# one_dollar_boad_beta4.net
KiCad netlist of a schematic drawn in EAGLE
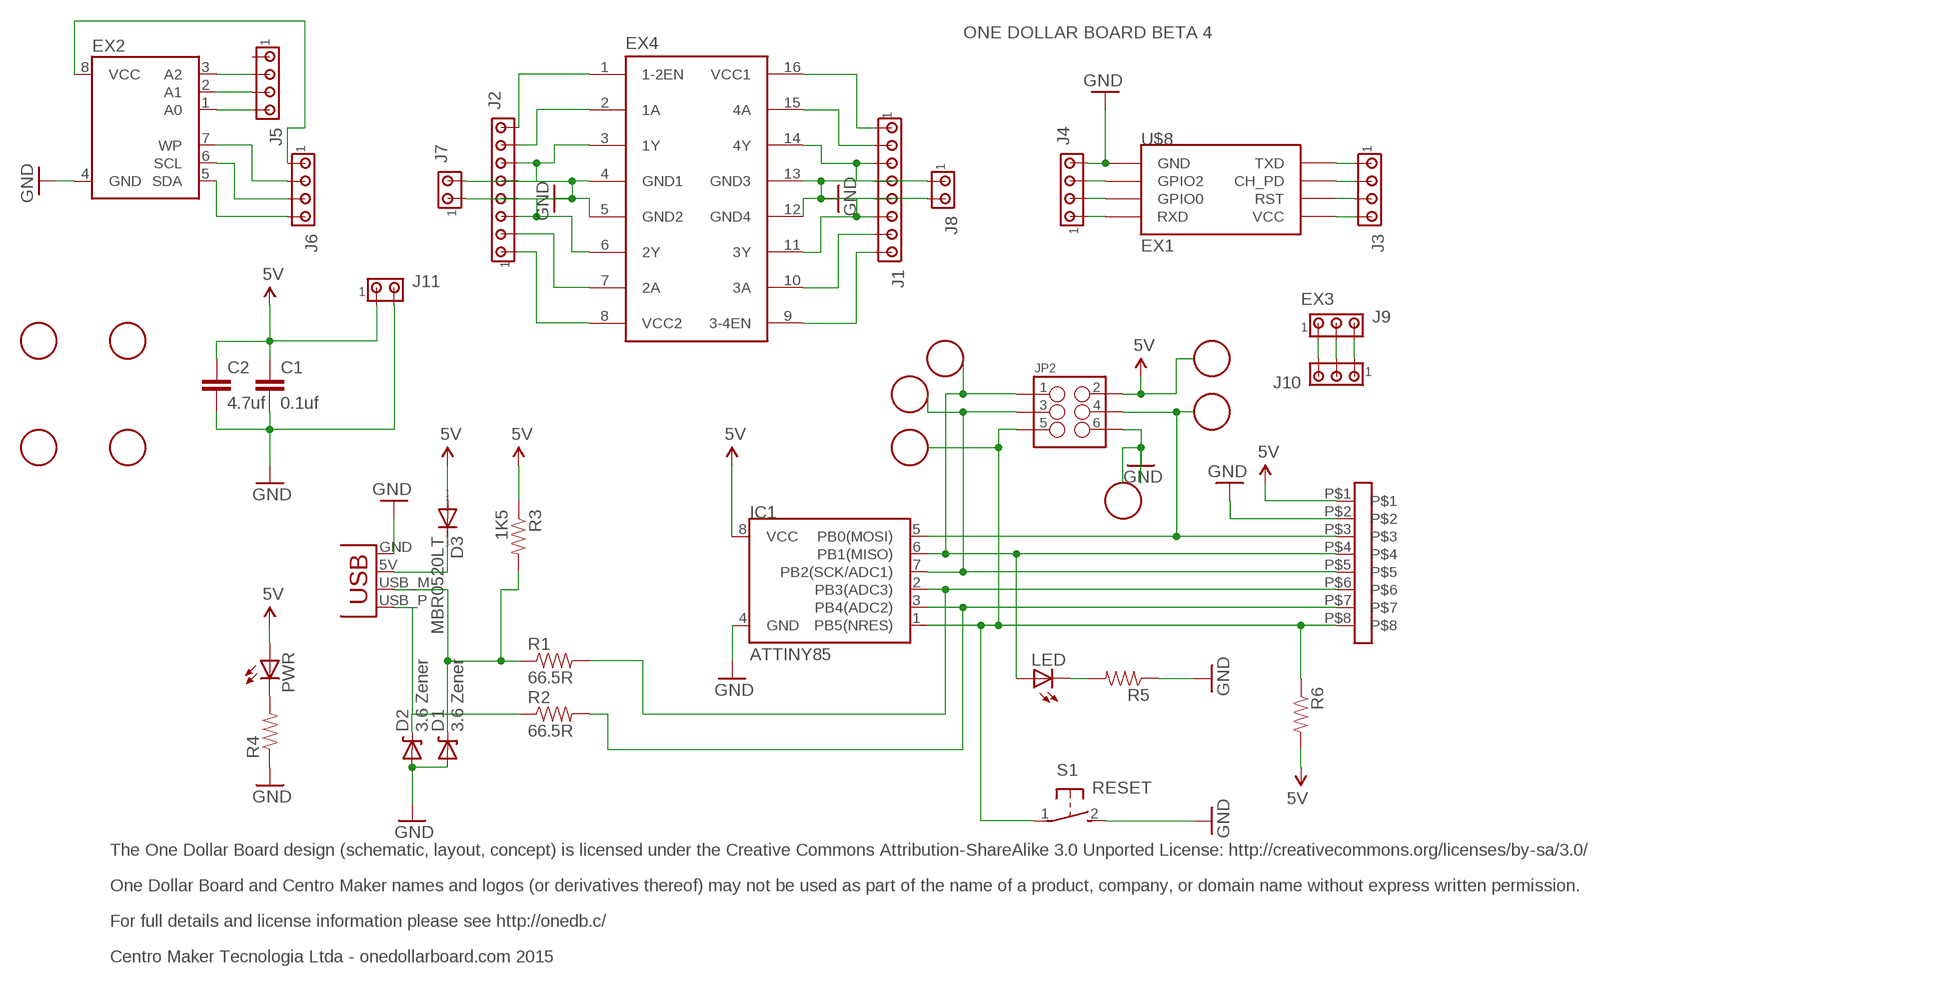
[diagram p0: schematic, sheet 1]

(export (version "E")
  (design (tool "Eeschema 10.0.6"))
  (components
    (comp (ref "C1")
      (value "0.1uf")
      (footprint "eagle-import:0402-CAP")
      (libsource (lib "eagle-import") (part "CAP0402-CAP"))
    )
    (comp (ref "C2")
      (value "4.7uf")
      (footprint "eagle-import:0805")
      (libsource (lib "eagle-import") (part "CAP0805"))
    )
    (comp (ref "CONNECTORBAR1")
      (value ".")
      (footprint "eagle-import:FEMEABARRA01X08")
      (libsource (lib "eagle-import") (part "FAMALEBAR01X08"))
    )
    (comp (ref "D1")
      (value "3.6 Zener")
      (footprint "eagle-import:SOD-323")
      (libsource (lib "eagle-import") (part "DIODE-ZENER-BZT52"))
    )
    (comp (ref "D2")
      (value "3.6 Zener")
      (footprint "eagle-import:SOD-323")
      (libsource (lib "eagle-import") (part "DIODE-ZENER-BZT52"))
    )
    (comp (ref "D3")
      (value "MBR0520LT")
      (footprint "eagle-import:SOD123")
      (libsource (lib "eagle-import") (part "MBR0520LT"))
    )
    (comp (ref "EX2")
      (value "AT24CP")
      (footprint "eagle-import:DIL08")
      (fields (field (name "MPN") "AT24C1024BW-SH-B"))
      (libsource (lib "eagle-import") (part "AT24CP"))
    )
    (comp (ref "EX4")
      (value "L293D")
      (footprint "eagle-import:DIL16")
      (libsource (lib "eagle-import") (part "L293D"))
    )
    (comp (ref "IC1")
      (value "ATTINY85")
      (footprint "eagle-import:SO08-EIAJ")
      (libsource (lib "eagle-import") (part "ATTINY45"))
    )
    (comp (ref "ICSP1")
      (value "ICSP")
      (footprint "eagle-import:ICSP")
      (libsource (lib "eagle-import") (part "ICSP"))
    )
    (comp (ref "ICSP2")
      (value "ICSP")
      (footprint "eagle-import:ICSP")
      (libsource (lib "eagle-import") (part "ICSP"))
    )
    (comp (ref "ICSP3")
      (value "ICSP")
      (footprint "eagle-import:ICSP")
      (libsource (lib "eagle-import") (part "ICSP"))
    )
    (comp (ref "ICSP4")
      (value "ICSP")
      (footprint "eagle-import:ICSP")
      (libsource (lib "eagle-import") (part "ICSP"))
    )
    (comp (ref "ICSP5")
      (value "ICSP")
      (footprint "eagle-import:ICSP")
      (libsource (lib "eagle-import") (part "ICSP"))
    )
    (comp (ref "ICSP6")
      (value "ICSP")
      (footprint "eagle-import:ICSP")
      (libsource (lib "eagle-import") (part "ICSP"))
    )
    (comp (ref "J1")
      (value "MTA08-100")
      (footprint "eagle-import:10X08MTA")
      (libsource (lib "eagle-import") (part "MTA08-100"))
    )
    (comp (ref "J2")
      (value "MTA08-100")
      (footprint "eagle-import:10X08MTA")
      (libsource (lib "eagle-import") (part "MTA08-100"))
    )
    (comp (ref "J3")
      (value "MTA04-100")
      (footprint "eagle-import:10X04MTA")
      (libsource (lib "eagle-import") (part "MTA04-100"))
    )
    (comp (ref "J4")
      (value "MTA04-100")
      (footprint "eagle-import:10X04MTA")
      (libsource (lib "eagle-import") (part "MTA04-100"))
    )
    (comp (ref "J5")
      (value "MTA04-100")
      (footprint "eagle-import:10X04MTA")
      (libsource (lib "eagle-import") (part "MTA04-100"))
    )
    (comp (ref "J6")
      (value "MTA04-100")
      (footprint "eagle-import:10X04MTA")
      (libsource (lib "eagle-import") (part "MTA04-100"))
    )
    (comp (ref "J7")
      (value "MTA02-100")
      (footprint "eagle-import:10X02MTA")
      (libsource (lib "eagle-import") (part "MTA02-100"))
    )
    (comp (ref "J8")
      (value "MTA02-100")
      (footprint "eagle-import:10X02MTA")
      (libsource (lib "eagle-import") (part "MTA02-100"))
    )
    (comp (ref "J9")
      (value "MTA03-100")
      (footprint "eagle-import:10X03MTA")
      (libsource (lib "eagle-import") (part "MTA03-100"))
    )
    (comp (ref "J10")
      (value "MTA03-100")
      (footprint "eagle-import:10X03MTA")
      (libsource (lib "eagle-import") (part "MTA03-100"))
    )
    (comp (ref "J11")
      (value "MTA02-100")
      (footprint "eagle-import:10X02MTA")
      (libsource (lib "eagle-import") (part "MTA02-100"))
    )
    (comp (ref "JP2")
      (value "M03X22X3_SILK_MALE_PTH")
      (footprint "eagle-import:2X3")
      (libsource (lib "eagle-import") (part "M03X22X3_SILK_MALE_PTH"))
    )
    (comp (ref "LED")
      (value "LED0603")
      (footprint "eagle-import:LED-0603")
      (libsource (lib "eagle-import") (part "LED0603"))
    )
    (comp (ref "PWR")
      (value "LED0603")
      (footprint "eagle-import:LED-0603")
      (libsource (lib "eagle-import") (part "LED0603"))
    )
    (comp (ref "R1")
      (value "66.5R")
      (footprint "eagle-import:0402-RES")
      (libsource (lib "eagle-import") (part "RESISTOR0402-RES"))
    )
    (comp (ref "R2")
      (value "66.5R")
      (footprint "eagle-import:0402-RES")
      (libsource (lib "eagle-import") (part "RESISTOR0402-RES"))
    )
    (comp (ref "R3")
      (value "1K5")
      (footprint "eagle-import:0402-RES")
      (libsource (lib "eagle-import") (part "RESISTOR0402-RES"))
    )
    (comp (ref "R4")
      (value "RESISTOR0402-RES")
      (footprint "eagle-import:0402-RES")
      (libsource (lib "eagle-import") (part "RESISTOR0402-RES"))
    )
    (comp (ref "R5")
      (value "RESISTOR0402-RES")
      (footprint "eagle-import:0402-RES")
      (libsource (lib "eagle-import") (part "RESISTOR0402-RES"))
    )
    (comp (ref "R6")
      (value "RESISTOR0402-RES")
      (footprint "eagle-import:0402-RES")
      (libsource (lib "eagle-import") (part "RESISTOR0402-RES"))
    )
    (comp (ref "S1")
      (value "RESET")
      (footprint "eagle-import:DTSM-3")
      (libsource (lib "eagle-import") (part "DTSM-3"))
    )
    (comp (ref "U$8")
      (value "EX1")
      (footprint "eagle-import:ESP01")
      (libsource (lib "eagle-import") (part "ESP01"))
    )
    (comp (ref "U$9")
      (value "ARDUINOPINAGEM")
      (footprint "eagle-import:ARDUINOPINAGEM")
      (libsource (lib "eagle-import") (part "ARDUINOPINAGEM"))
    )
    (comp (ref "X1")
      (value "USBPCB")
      (footprint "eagle-import:USB-A-PCB")
      (libsource (lib "eagle-import") (part "USBPCB"))
    )
  )
  (nets
    (net (code "1") (name "5V") (class "Default")
      (node (ref "C1") (pin "1") (pinfunction "1_1") (pintype "passive"))
      (node (ref "C2") (pin "1") (pinfunction "1_1") (pintype "passive"))
      (node (ref "CONNECTORBAR1") (pin "P$1") (pinfunction "P$1_P$1") (pintype "bidirectional"))
      (node (ref "D3") (pin "A") (pinfunction "A_A") (pintype "passive"))
      (node (ref "IC1") (pin "8") (pinfunction "VCC_8") (pintype "bidirectional"))
      (node (ref "J11") (pin "1") (pinfunction "1_1") (pintype "passive"))
      (node (ref "JP2") (pin "2") (pinfunction "2_2") (pintype "bidirectional"))
      (node (ref "PWR") (pin "A") (pinfunction "A_A") (pintype "passive"))
      (node (ref "R3") (pin "1") (pinfunction "1_1") (pintype "passive"))
      (node (ref "R6") (pin "2") (pinfunction "2_2") (pintype "passive"))
    )
    (net (code "2") (name "GND") (class "Default")
      (node (ref "C1") (pin "2") (pinfunction "2_2") (pintype "passive"))
      (node (ref "C2") (pin "2") (pinfunction "2_2") (pintype "passive"))
      (node (ref "CONNECTORBAR1") (pin "P$2") (pinfunction "P$2_P$2") (pintype "bidirectional"))
      (node (ref "D1") (pin "2") (pinfunction "A_2") (pintype "passive"))
      (node (ref "D2") (pin "2") (pinfunction "A_2") (pintype "passive"))
      (node (ref "EX2") (pin "4") (pinfunction "GND_4") (pintype "power_in"))
      (node (ref "EX4") (pin "12") (pinfunction "GND4_12") (pintype "power_in"))
      (node (ref "EX4") (pin "13") (pinfunction "GND3_13") (pintype "power_in"))
      (node (ref "EX4") (pin "4") (pinfunction "GND1_4") (pintype "power_in"))
      (node (ref "EX4") (pin "5") (pinfunction "GND2_5") (pintype "power_in"))
      (node (ref "IC1") (pin "4") (pinfunction "GND_4") (pintype "bidirectional"))
      (node (ref "J1") (pin "4") (pinfunction "4_4") (pintype "passive"))
      (node (ref "J1") (pin "5") (pinfunction "5_5") (pintype "passive"))
      (node (ref "J11") (pin "2") (pinfunction "2_2") (pintype "passive"))
      (node (ref "J2") (pin "4") (pinfunction "4_4") (pintype "passive"))
      (node (ref "J2") (pin "5") (pinfunction "5_5") (pintype "passive"))
      (node (ref "J4") (pin "4") (pinfunction "4_4") (pintype "passive"))
      (node (ref "JP2") (pin "6") (pinfunction "6_6") (pintype "bidirectional"))
      (node (ref "R4") (pin "1") (pinfunction "1_1") (pintype "passive"))
      (node (ref "R5") (pin "1") (pinfunction "1_1") (pintype "passive"))
      (node (ref "S1") (pin "2") (pinfunction "2_2") (pintype "passive"))
      (node (ref "U$8") (pin "GND") (pinfunction "GND_GND") (pintype "bidirectional"))
      (node (ref "X1") (pin "GND") (pinfunction "GND_GND") (pintype "bidirectional"))
    )
    (net (code "3") (name "Net-(D1-C)") (class "Default")
      (node (ref "D1") (pin "1") (pinfunction "C_1") (pintype "passive"))
      (node (ref "R1") (pin "1") (pinfunction "1_1") (pintype "passive"))
      (node (ref "R3") (pin "2") (pinfunction "2_2") (pintype "passive"))
      (node (ref "X1") (pin "USB_M") (pinfunction "D-_USB_M") (pintype "bidirectional"))
    )
    (net (code "4") (name "Net-(D2-C)") (class "Default")
      (node (ref "D2") (pin "1") (pinfunction "C_1") (pintype "passive"))
      (node (ref "R2") (pin "1") (pinfunction "1_1") (pintype "passive"))
      (node (ref "X1") (pin "USB_P") (pinfunction "D+_USB_P") (pintype "bidirectional"))
    )
    (net (code "5") (name "Net-(EX2-A0)") (class "Default")
      (node (ref "EX2") (pin "1") (pinfunction "A0_1") (pintype "input"))
      (node (ref "J5") (pin "4") (pinfunction "4_4") (pintype "passive"))
    )
    (net (code "6") (name "Net-(EX2-A1)") (class "Default")
      (node (ref "EX2") (pin "2") (pinfunction "A1_2") (pintype "input"))
      (node (ref "J5") (pin "3") (pinfunction "3_3") (pintype "passive"))
    )
    (net (code "7") (name "Net-(EX2-A2)") (class "Default")
      (node (ref "EX2") (pin "3") (pinfunction "A2_3") (pintype "input"))
      (node (ref "J5") (pin "2") (pinfunction "2_2") (pintype "passive"))
    )
    (net (code "8") (name "Net-(EX2-SCL)") (class "Default")
      (node (ref "EX2") (pin "6") (pinfunction "SCL_6") (pintype "bidirectional"))
      (node (ref "J6") (pin "3") (pinfunction "3_3") (pintype "passive"))
    )
    (net (code "9") (name "Net-(EX2-SDA)") (class "Default")
      (node (ref "EX2") (pin "5") (pinfunction "SDA_5") (pintype "bidirectional"))
      (node (ref "J6") (pin "4") (pinfunction "4_4") (pintype "passive"))
    )
    (net (code "10") (name "Net-(EX2-VCC)") (class "Default")
      (node (ref "EX2") (pin "8") (pinfunction "VCC_8") (pintype "power_in"))
      (node (ref "J6") (pin "1") (pinfunction "1_1") (pintype "passive"))
    )
    (net (code "11") (name "Net-(EX2-WP)") (class "Default")
      (node (ref "EX2") (pin "7") (pinfunction "WP_7") (pintype "input"))
      (node (ref "J6") (pin "2") (pinfunction "2_2") (pintype "passive"))
    )
    (net (code "12") (name "Net-(EX4-1-2EN)") (class "Default")
      (node (ref "EX4") (pin "1") (pinfunction "1-2EN_1") (pintype "input"))
      (node (ref "J2") (pin "8") (pinfunction "8_8") (pintype "passive"))
    )
    (net (code "13") (name "Net-(EX4-1A)") (class "Default")
      (node (ref "EX4") (pin "2") (pinfunction "1A_2") (pintype "input"))
      (node (ref "J2") (pin "7") (pinfunction "7_7") (pintype "passive"))
    )
    (net (code "14") (name "Net-(EX4-1Y)") (class "Default")
      (node (ref "EX4") (pin "3") (pinfunction "1Y_3") (pintype "output"))
      (node (ref "J2") (pin "6") (pinfunction "6_6") (pintype "passive"))
      (node (ref "J7") (pin "2") (pinfunction "2_2") (pintype "passive"))
    )
    (net (code "15") (name "Net-(EX4-2A)") (class "Default")
      (node (ref "EX4") (pin "7") (pinfunction "2A_7") (pintype "input"))
      (node (ref "J2") (pin "2") (pinfunction "2_2") (pintype "passive"))
    )
    (net (code "16") (name "Net-(EX4-2Y)") (class "Default")
      (node (ref "EX4") (pin "6") (pinfunction "2Y_6") (pintype "output"))
      (node (ref "J2") (pin "3") (pinfunction "3_3") (pintype "passive"))
      (node (ref "J7") (pin "1") (pinfunction "1_1") (pintype "passive"))
    )
    (net (code "17") (name "Net-(EX4-3-4EN)") (class "Default")
      (node (ref "EX4") (pin "9") (pinfunction "3-4EN_9") (pintype "input"))
      (node (ref "J1") (pin "8") (pinfunction "8_8") (pintype "passive"))
    )
    (net (code "18") (name "Net-(EX4-3A)") (class "Default")
      (node (ref "EX4") (pin "10") (pinfunction "3A_10") (pintype "input"))
      (node (ref "J1") (pin "7") (pinfunction "7_7") (pintype "passive"))
    )
    (net (code "19") (name "Net-(EX4-3Y)") (class "Default")
      (node (ref "EX4") (pin "11") (pinfunction "3Y_11") (pintype "output"))
      (node (ref "J1") (pin "6") (pinfunction "6_6") (pintype "passive"))
      (node (ref "J8") (pin "2") (pinfunction "2_2") (pintype "passive"))
    )
    (net (code "20") (name "Net-(EX4-4A)") (class "Default")
      (node (ref "EX4") (pin "15") (pinfunction "4A_15") (pintype "input"))
      (node (ref "J1") (pin "2") (pinfunction "2_2") (pintype "passive"))
    )
    (net (code "21") (name "Net-(EX4-4Y)") (class "Default")
      (node (ref "EX4") (pin "14") (pinfunction "4Y_14") (pintype "output"))
      (node (ref "J1") (pin "3") (pinfunction "3_3") (pintype "passive"))
      (node (ref "J8") (pin "1") (pinfunction "1_1") (pintype "passive"))
    )
    (net (code "22") (name "Net-(EX4-VCC1)") (class "Default")
      (node (ref "EX4") (pin "16") (pinfunction "VCC1_16") (pintype "power_in"))
      (node (ref "J1") (pin "1") (pinfunction "1_1") (pintype "passive"))
    )
    (net (code "23") (name "Net-(EX4-VCC2)") (class "Default")
      (node (ref "EX4") (pin "8") (pinfunction "VCC2_8") (pintype "power_in"))
      (node (ref "J2") (pin "1") (pinfunction "1_1") (pintype "passive"))
    )
    (net (code "24") (name "Net-(IC1-PB0(MOSI))") (class "Default")
      (node (ref "CONNECTORBAR1") (pin "P$3") (pinfunction "P$3_P$3") (pintype "bidirectional"))
      (node (ref "IC1") (pin "5") (pinfunction "PB0(MOSI)_5") (pintype "bidirectional"))
      (node (ref "JP2") (pin "4") (pinfunction "4_4") (pintype "bidirectional"))
    )
    (net (code "25") (name "Net-(IC1-PB1(MISO))") (class "Default")
      (node (ref "CONNECTORBAR1") (pin "P$4") (pinfunction "P$4_P$4") (pintype "bidirectional"))
      (node (ref "IC1") (pin "6") (pinfunction "PB1(MISO)_6") (pintype "bidirectional"))
      (node (ref "JP2") (pin "1") (pinfunction "1_1") (pintype "bidirectional"))
      (node (ref "LED") (pin "A") (pinfunction "A_A") (pintype "passive"))
    )
    (net (code "26") (name "Net-(IC1-PB2(SCK{slash}ADC1))") (class "Default")
      (node (ref "CONNECTORBAR1") (pin "P$5") (pinfunction "P$5_P$5") (pintype "bidirectional"))
      (node (ref "IC1") (pin "7") (pinfunction "PB2(SCK/ADC1)_7") (pintype "bidirectional"))
      (node (ref "JP2") (pin "3") (pinfunction "3_3") (pintype "bidirectional"))
    )
    (net (code "27") (name "Net-(IC1-PB3(ADC3))") (class "Default")
      (node (ref "CONNECTORBAR1") (pin "P$6") (pinfunction "P$6_P$6") (pintype "bidirectional"))
      (node (ref "IC1") (pin "2") (pinfunction "PB3(ADC3)_2") (pintype "bidirectional"))
      (node (ref "R1") (pin "2") (pinfunction "2_2") (pintype "passive"))
    )
    (net (code "28") (name "Net-(IC1-PB4(ADC2))") (class "Default")
      (node (ref "CONNECTORBAR1") (pin "P$7") (pinfunction "P$7_P$7") (pintype "bidirectional"))
      (node (ref "IC1") (pin "3") (pinfunction "PB4(ADC2)_3") (pintype "bidirectional"))
      (node (ref "R2") (pin "2") (pinfunction "2_2") (pintype "passive"))
    )
    (net (code "29") (name "Net-(IC1-PB5(NRES))") (class "Default")
      (node (ref "CONNECTORBAR1") (pin "P$8") (pinfunction "P$8_P$8") (pintype "bidirectional"))
      (node (ref "IC1") (pin "1") (pinfunction "PB5(NRES)_1") (pintype "bidirectional"))
      (node (ref "JP2") (pin "5") (pinfunction "5_5") (pintype "bidirectional"))
      (node (ref "R6") (pin "1") (pinfunction "1_1") (pintype "passive"))
      (node (ref "S1") (pin "1") (pinfunction "1_1") (pintype "passive"))
    )
    (net (code "30") (name "Net-(J3-Pad2)") (class "Default")
      (node (ref "J3") (pin "2") (pinfunction "2_2") (pintype "passive"))
      (node (ref "U$8") (pin "CH_PD") (pinfunction "CH_PD_CH_PD") (pintype "bidirectional"))
    )
    (net (code "31") (name "Net-(J3-Pad3)") (class "Default")
      (node (ref "J3") (pin "3") (pinfunction "3_3") (pintype "passive"))
      (node (ref "U$8") (pin "RST") (pinfunction "RST_RST") (pintype "bidirectional"))
    )
    (net (code "32") (name "Net-(J3-Pad4)") (class "Default")
      (node (ref "J3") (pin "4") (pinfunction "4_4") (pintype "passive"))
      (node (ref "U$8") (pin "VCC") (pinfunction "VCC_VCC") (pintype "bidirectional"))
    )
    (net (code "33") (name "Net-(J4-Pad2)") (class "Default")
      (node (ref "J4") (pin "2") (pinfunction "2_2") (pintype "passive"))
      (node (ref "U$8") (pin "GPIO0") (pinfunction "GPIO0_GPIO0") (pintype "bidirectional"))
    )
    (net (code "34") (name "Net-(J4-Pad3)") (class "Default")
      (node (ref "J4") (pin "3") (pinfunction "3_3") (pintype "passive"))
      (node (ref "U$8") (pin "GPIO2") (pinfunction "GPIO2_GPIO2") (pintype "bidirectional"))
    )
    (net (code "35") (name "Net-(J10-Pad1)") (class "Default")
      (node (ref "J10") (pin "1") (pinfunction "1_1") (pintype "passive"))
      (node (ref "J9") (pin "3") (pinfunction "3_3") (pintype "passive"))
    )
    (net (code "36") (name "Net-(J10-Pad2)") (class "Default")
      (node (ref "J10") (pin "2") (pinfunction "2_2") (pintype "passive"))
      (node (ref "J9") (pin "2") (pinfunction "2_2") (pintype "passive"))
    )
    (net (code "37") (name "Net-(J10-Pad3)") (class "Default")
      (node (ref "J10") (pin "3") (pinfunction "3_3") (pintype "passive"))
      (node (ref "J9") (pin "1") (pinfunction "1_1") (pintype "passive"))
    )
    (net (code "38") (name "Net-(LED-PadC)") (class "Default")
      (node (ref "LED") (pin "C") (pinfunction "C_C") (pintype "passive"))
      (node (ref "R5") (pin "2") (pinfunction "2_2") (pintype "passive"))
    )
    (net (code "39") (name "Net-(PWR-PadC)") (class "Default")
      (node (ref "PWR") (pin "C") (pinfunction "C_C") (pintype "passive"))
      (node (ref "R4") (pin "2") (pinfunction "2_2") (pintype "passive"))
    )
    (net (code "40") (name "Net-(U$8-RXD)") (class "Default")
      (node (ref "J4") (pin "1") (pinfunction "1_1") (pintype "passive"))
      (node (ref "U$8") (pin "RX") (pinfunction "RXD_RX") (pintype "bidirectional"))
    )
    (net (code "41") (name "Net-(U$8-TXD)") (class "Default")
      (node (ref "J3") (pin "1") (pinfunction "1_1") (pintype "passive"))
      (node (ref "U$8") (pin "TX") (pinfunction "TXD_TX") (pintype "bidirectional"))
    )
    (net (code "42") (name "Net-(X1-VBUS)") (class "Default")
      (node (ref "D3") (pin "C") (pinfunction "C_C") (pintype "passive"))
      (node (ref "X1") (pin "5V") (pinfunction "VBUS_5V") (pintype "bidirectional"))
    )
    (net (code "43") (name "unconnected-(J5-Pad1)") (class "Default")
      (node (ref "J5") (pin "1") (pinfunction "1_1") (pintype "passive"))
    )
  )
)
